# telescopicrobot.net
KiCad netlist of a schematic drawn in EAGLE
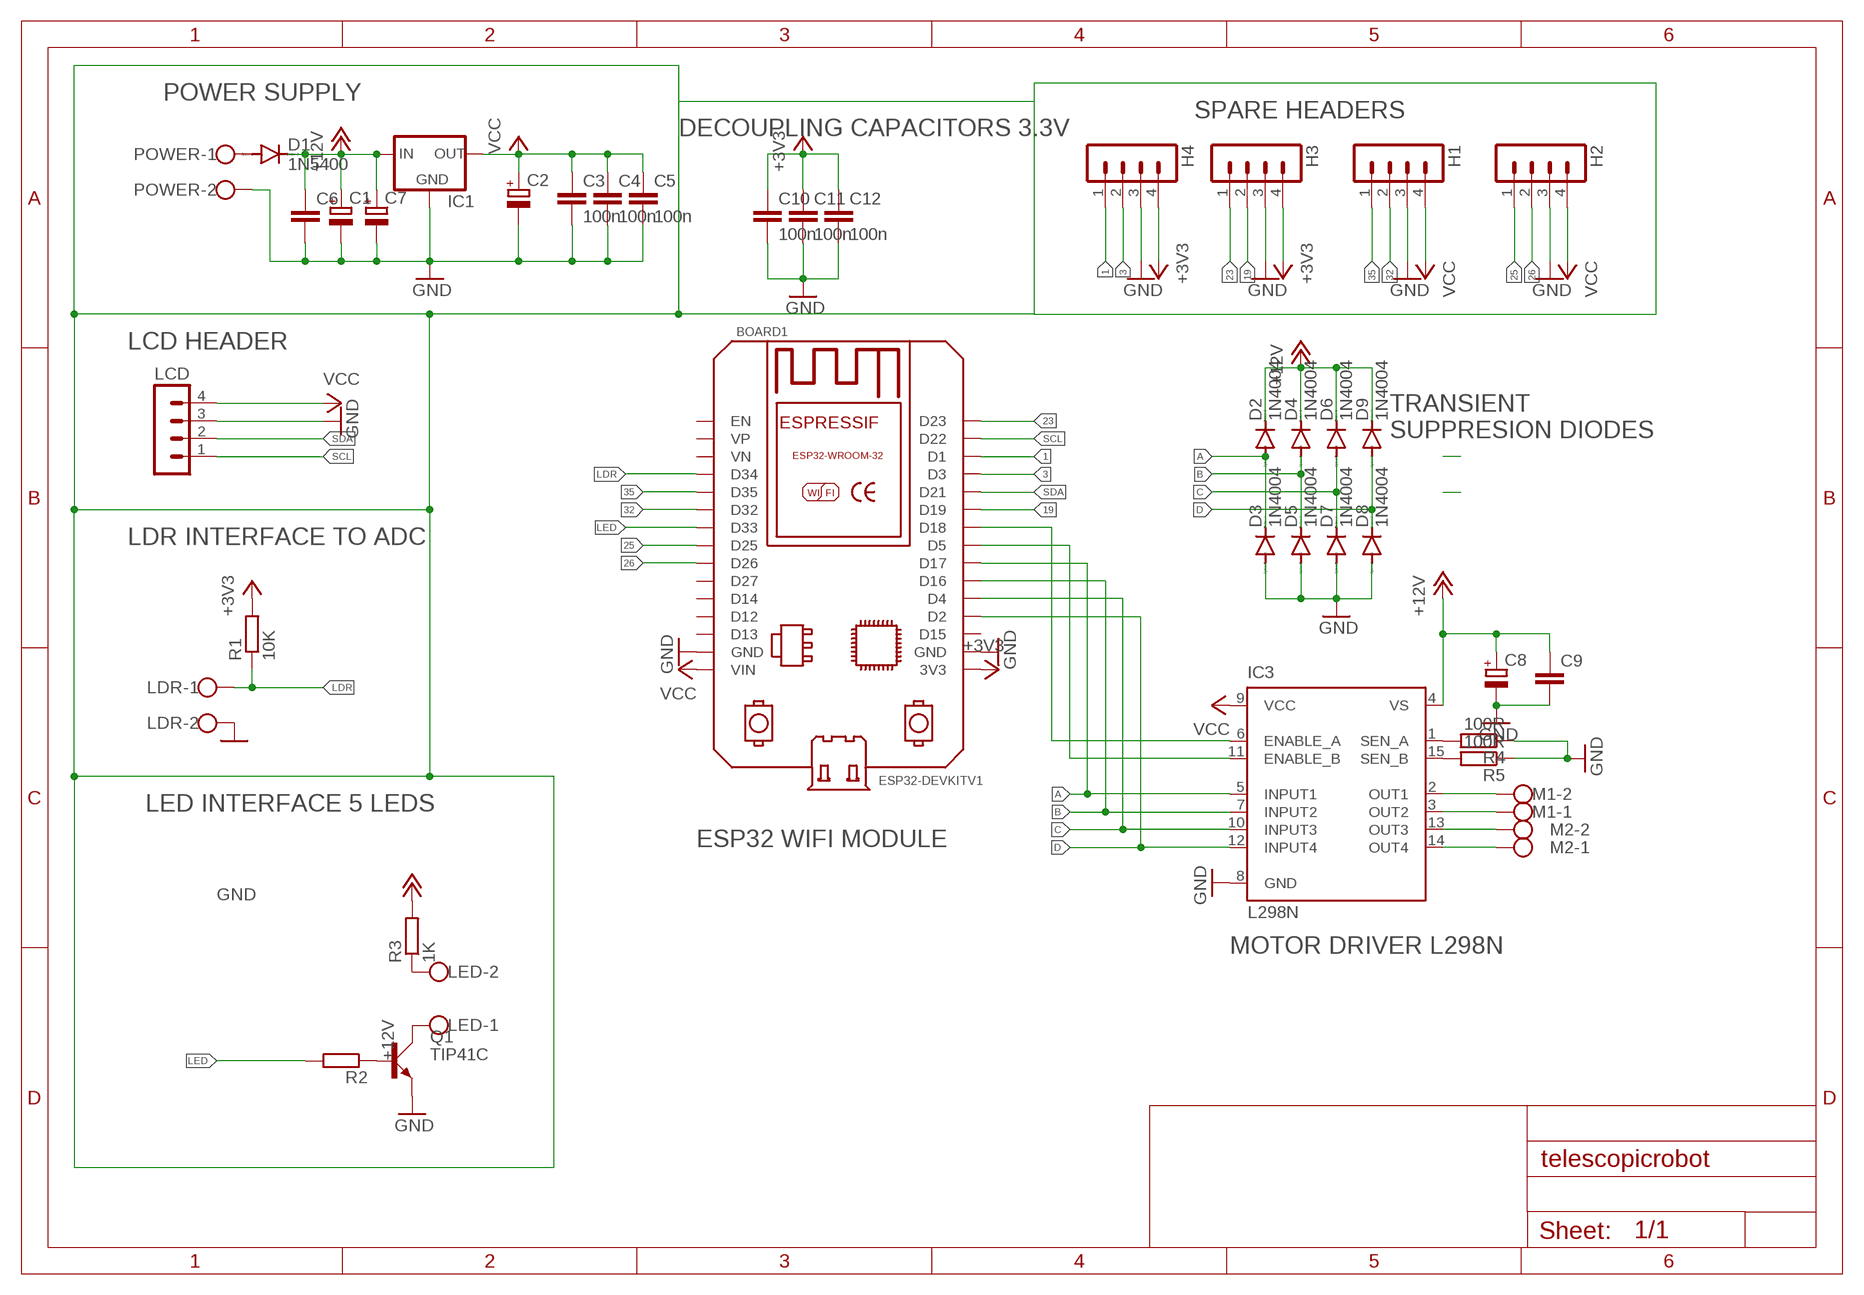
[diagram p0: schematic, sheet 1]

(export (version "E")
  (design (tool "Eeschema 10.0.6"))
  (components
    (comp (ref "BOARD1")
      (value "ESP32DEVKITV1")
      (footprint "eagle-import:ESP32-DEVKITV1")
      (libsource (lib "eagle-import") (part "ESP32DEVKITV1"))
    )
    (comp (ref "C1")
      (value "CPOL-EUE5-10.5")
      (footprint "eagle-import:E5-10,5")
      (libsource (lib "eagle-import") (part "CPOL-EUE5-10.5"))
    )
    (comp (ref "C2")
      (value "CPOL-EUE2.5-5")
      (footprint "eagle-import:E2,5-5")
      (libsource (lib "eagle-import") (part "CPOL-EUE2.5-5"))
    )
    (comp (ref "C3")
      (value "100n")
      (footprint "eagle-import:C2.5-3")
      (libsource (lib "eagle-import") (part "C2,5-3"))
    )
    (comp (ref "C4")
      (value "100n")
      (footprint "eagle-import:C2.5-3")
      (libsource (lib "eagle-import") (part "C2,5-3"))
    )
    (comp (ref "C5")
      (value "100n")
      (footprint "eagle-import:C2.5-3")
      (libsource (lib "eagle-import") (part "C2,5-3"))
    )
    (comp (ref "C6")
      (value "C2,5-3")
      (footprint "eagle-import:C2.5-3")
      (libsource (lib "eagle-import") (part "C2,5-3"))
    )
    (comp (ref "C7")
      (value "CPOL-EUE5-10.5")
      (footprint "eagle-import:E5-10,5")
      (libsource (lib "eagle-import") (part "CPOL-EUE5-10.5"))
    )
    (comp (ref "C8")
      (value "CPOL-EUE5-10.5")
      (footprint "eagle-import:E5-10,5")
      (libsource (lib "eagle-import") (part "CPOL-EUE5-10.5"))
    )
    (comp (ref "C9")
      (value "C2,5-3")
      (footprint "eagle-import:C2.5-3")
      (libsource (lib "eagle-import") (part "C2,5-3"))
    )
    (comp (ref "C10")
      (value "100n")
      (footprint "eagle-import:C2.5-3")
      (libsource (lib "eagle-import") (part "C2,5-3"))
    )
    (comp (ref "C11")
      (value "100n")
      (footprint "eagle-import:C2.5-3")
      (libsource (lib "eagle-import") (part "C2,5-3"))
    )
    (comp (ref "C12")
      (value "100n")
      (footprint "eagle-import:C2.5-3")
      (libsource (lib "eagle-import") (part "C2,5-3"))
    )
    (comp (ref "D1")
      (value "1N5400")
      (footprint "eagle-import:DO201-15")
      (libsource (lib "eagle-import") (part "1N5400"))
    )
    (comp (ref "D2")
      (value "1N4004")
      (footprint "eagle-import:DO41-10")
      (libsource (lib "eagle-import") (part "1N4004"))
    )
    (comp (ref "D3")
      (value "1N4004")
      (footprint "eagle-import:DO41-10")
      (libsource (lib "eagle-import") (part "1N4004"))
    )
    (comp (ref "D4")
      (value "1N4004")
      (footprint "eagle-import:DO41-10")
      (libsource (lib "eagle-import") (part "1N4004"))
    )
    (comp (ref "D5")
      (value "1N4004")
      (footprint "eagle-import:DO41-10")
      (libsource (lib "eagle-import") (part "1N4004"))
    )
    (comp (ref "D6")
      (value "1N4004")
      (footprint "eagle-import:DO41-10")
      (libsource (lib "eagle-import") (part "1N4004"))
    )
    (comp (ref "D7")
      (value "1N4004")
      (footprint "eagle-import:DO41-10")
      (libsource (lib "eagle-import") (part "1N4004"))
    )
    (comp (ref "D8")
      (value "1N4004")
      (footprint "eagle-import:DO41-10")
      (libsource (lib "eagle-import") (part "1N4004"))
    )
    (comp (ref "D9")
      (value "1N4004")
      (footprint "eagle-import:DO41-10")
      (libsource (lib "eagle-import") (part "1N4004"))
    )
    (comp (ref "H1")
      (value "MA04-1")
      (footprint "eagle-import:MA04-1")
      (libsource (lib "eagle-import") (part "MA04-1"))
    )
    (comp (ref "H2")
      (value "MA04-1")
      (footprint "eagle-import:MA04-1")
      (libsource (lib "eagle-import") (part "MA04-1"))
    )
    (comp (ref "H3")
      (value "MA04-1")
      (footprint "eagle-import:MA04-1")
      (libsource (lib "eagle-import") (part "MA04-1"))
    )
    (comp (ref "H4")
      (value "MA04-1")
      (footprint "eagle-import:MA04-1")
      (libsource (lib "eagle-import") (part "MA04-1"))
    )
    (comp (ref "IC1")
      (value "78XXS")
      (footprint "eagle-import:78XXS")
      (libsource (lib "eagle-import") (part "78XXS"))
    )
    (comp (ref "IC3")
      (value "L298N")
      (footprint "eagle-import:MULTIWATT-15")
      (libsource (lib "eagle-import") (part "L298N"))
    )
    (comp (ref "LCD")
      (value "MA04-1")
      (footprint "eagle-import:MA04-1")
      (libsource (lib "eagle-import") (part "MA04-1"))
    )
    (comp (ref "LDR")
      (value "W237-102")
      (footprint "eagle-import:W237-102")
      (fields (field (name "MPN") "237-102"))
      (libsource (lib "eagle-import") (part "W237-102"))
    )
    (comp (ref "LED")
      (value "W237-102")
      (footprint "eagle-import:W237-102")
      (fields (field (name "MPN") "237-102"))
      (libsource (lib "eagle-import") (part "W237-102"))
    )
    (comp (ref "M1")
      (value "W237-102")
      (footprint "eagle-import:W237-102")
      (fields (field (name "MPN") "237-102"))
      (libsource (lib "eagle-import") (part "W237-102"))
    )
    (comp (ref "M2")
      (value "W237-102")
      (footprint "eagle-import:W237-102")
      (fields (field (name "MPN") "237-102"))
      (libsource (lib "eagle-import") (part "W237-102"))
    )
    (comp (ref "POWER")
      (value "W237-102")
      (footprint "eagle-import:W237-102")
      (fields (field (name "MPN") "237-102"))
      (libsource (lib "eagle-import") (part "W237-102"))
    )
    (comp (ref "Q1")
      (value "TIP41C")
      (footprint "eagle-import:TO220AV")
      (libsource (lib "eagle-import") (part "TIP41C"))
    )
    (comp (ref "R1")
      (value "10K")
      (footprint "eagle-import:0207_12")
      (libsource (lib "eagle-import") (part "R-EU_0207/12"))
    )
    (comp (ref "R2")
      (value "R-EU_0207/12")
      (footprint "eagle-import:0207_12")
      (libsource (lib "eagle-import") (part "R-EU_0207/12"))
    )
    (comp (ref "R3")
      (value "1K")
      (footprint "eagle-import:0207_12")
      (libsource (lib "eagle-import") (part "resistor_348_R-EU_0207/12"))
    )
    (comp (ref "R4")
      (value "100R")
      (footprint "eagle-import:0207_12")
      (libsource (lib "eagle-import") (part "resistor_348_R-EU_0207/12"))
    )
    (comp (ref "R5")
      (value "100R")
      (footprint "eagle-import:0207_12")
      (libsource (lib "eagle-import") (part "resistor_348_R-EU_0207/12"))
    )
  )
  (nets
    (net (code "1") (name "+3V3") (class "Default")
      (node (ref "BOARD1") (pin "3V3") (pinfunction "3V3_3V3") (pintype "bidirectional"))
      (node (ref "C10") (pin "1") (pinfunction "1_1") (pintype "passive"))
      (node (ref "C11") (pin "1") (pinfunction "1_1") (pintype "passive"))
      (node (ref "C12") (pin "1") (pinfunction "1_1") (pintype "passive"))
      (node (ref "H3") (pin "4") (pinfunction "4_4") (pintype "passive"))
      (node (ref "H4") (pin "4") (pinfunction "4_4") (pintype "passive"))
      (node (ref "R1") (pin "2") (pinfunction "2_2") (pintype "passive"))
    )
    (net (code "2") (name "+12V") (class "Default")
      (node (ref "C1") (pin "+") (pinfunction "+_+") (pintype "passive"))
      (node (ref "C6") (pin "1") (pinfunction "1_1") (pintype "passive"))
      (node (ref "C7") (pin "+") (pinfunction "+_+") (pintype "passive"))
      (node (ref "C8") (pin "+") (pinfunction "+_+") (pintype "passive"))
      (node (ref "C9") (pin "1") (pinfunction "1_1") (pintype "passive"))
      (node (ref "D1") (pin "C") (pinfunction "C_C") (pintype "passive"))
      (node (ref "D2") (pin "C") (pinfunction "C_C") (pintype "passive"))
      (node (ref "D4") (pin "C") (pinfunction "C_C") (pintype "passive"))
      (node (ref "D6") (pin "C") (pinfunction "C_C") (pintype "passive"))
      (node (ref "D9") (pin "C") (pinfunction "C_C") (pintype "passive"))
      (node (ref "IC1") (pin "IN") (pinfunction "IN_IN") (pintype "input"))
      (node (ref "IC3") (pin "4") (pinfunction "VS_4") (pintype "power_in"))
      (node (ref "R3") (pin "2") (pinfunction "2_2") (pintype "passive"))
    )
    (net (code "3") (name "1") (class "Default")
      (node (ref "BOARD1") (pin "D1") (pinfunction "D1_D1") (pintype "bidirectional"))
      (node (ref "H4") (pin "1") (pinfunction "1_1") (pintype "passive"))
    )
    (net (code "4") (name "3") (class "Default")
      (node (ref "BOARD1") (pin "D3") (pinfunction "D3_D3") (pintype "bidirectional"))
      (node (ref "H4") (pin "2") (pinfunction "2_2") (pintype "passive"))
    )
    (net (code "5") (name "19") (class "Default")
      (node (ref "BOARD1") (pin "D19") (pinfunction "D19_D19") (pintype "bidirectional"))
      (node (ref "H3") (pin "2") (pinfunction "2_2") (pintype "passive"))
    )
    (net (code "6") (name "23") (class "Default")
      (node (ref "BOARD1") (pin "D23") (pinfunction "D23_D23") (pintype "bidirectional"))
      (node (ref "H3") (pin "1") (pinfunction "1_1") (pintype "passive"))
    )
    (net (code "7") (name "25") (class "Default")
      (node (ref "BOARD1") (pin "D25") (pinfunction "D25_D25") (pintype "bidirectional"))
      (node (ref "H2") (pin "1") (pinfunction "1_1") (pintype "passive"))
    )
    (net (code "8") (name "26") (class "Default")
      (node (ref "BOARD1") (pin "D26") (pinfunction "D26_D26") (pintype "bidirectional"))
      (node (ref "H2") (pin "2") (pinfunction "2_2") (pintype "passive"))
    )
    (net (code "9") (name "32") (class "Default")
      (node (ref "BOARD1") (pin "D32") (pinfunction "D32_D32") (pintype "bidirectional"))
      (node (ref "H1") (pin "2") (pinfunction "2_2") (pintype "passive"))
    )
    (net (code "10") (name "35") (class "Default")
      (node (ref "BOARD1") (pin "D35") (pinfunction "D35_D35") (pintype "bidirectional"))
      (node (ref "H1") (pin "1") (pinfunction "1_1") (pintype "passive"))
    )
    (net (code "11") (name "A") (class "Default")
      (node (ref "BOARD1") (pin "D17") (pinfunction "D17_D17") (pintype "bidirectional"))
      (node (ref "D2") (pin "A") (pinfunction "A_A") (pintype "passive"))
      (node (ref "D3") (pin "C") (pinfunction "C_C") (pintype "passive"))
      (node (ref "IC3") (pin "5") (pinfunction "INPUT1_5") (pintype "input"))
    )
    (net (code "12") (name "B") (class "Default")
      (node (ref "BOARD1") (pin "D16") (pinfunction "D16_D16") (pintype "bidirectional"))
      (node (ref "D4") (pin "A") (pinfunction "A_A") (pintype "passive"))
      (node (ref "D5") (pin "C") (pinfunction "C_C") (pintype "passive"))
      (node (ref "IC3") (pin "7") (pinfunction "INPUT2_7") (pintype "input"))
    )
    (net (code "13") (name "C") (class "Default")
      (node (ref "BOARD1") (pin "D4") (pinfunction "D4_D4") (pintype "bidirectional"))
      (node (ref "D6") (pin "A") (pinfunction "A_A") (pintype "passive"))
      (node (ref "D7") (pin "C") (pinfunction "C_C") (pintype "passive"))
      (node (ref "IC3") (pin "10") (pinfunction "INPUT3_10") (pintype "input"))
    )
    (net (code "14") (name "D") (class "Default")
      (node (ref "BOARD1") (pin "D2") (pinfunction "D2_D2") (pintype "bidirectional"))
      (node (ref "D8") (pin "C") (pinfunction "C_C") (pintype "passive"))
      (node (ref "D9") (pin "A") (pinfunction "A_A") (pintype "passive"))
      (node (ref "IC3") (pin "12") (pinfunction "INPUT4_12") (pintype "input"))
    )
    (net (code "15") (name "GND") (class "Default")
      (node (ref "BOARD1") (pin "GND") (pinfunction "GND_GND") (pintype "bidirectional"))
      (node (ref "BOARD1") (pin "GND@1") (pinfunction "GND_GND@1") (pintype "bidirectional"))
      (node (ref "C1") (pin "-") (pinfunction "-_-") (pintype "passive"))
      (node (ref "C10") (pin "2") (pinfunction "2_2") (pintype "passive"))
      (node (ref "C11") (pin "2") (pinfunction "2_2") (pintype "passive"))
      (node (ref "C12") (pin "2") (pinfunction "2_2") (pintype "passive"))
      (node (ref "C2") (pin "-") (pinfunction "-_-") (pintype "passive"))
      (node (ref "C3") (pin "2") (pinfunction "2_2") (pintype "passive"))
      (node (ref "C4") (pin "2") (pinfunction "2_2") (pintype "passive"))
      (node (ref "C5") (pin "2") (pinfunction "2_2") (pintype "passive"))
      (node (ref "C6") (pin "2") (pinfunction "2_2") (pintype "passive"))
      (node (ref "C7") (pin "-") (pinfunction "-_-") (pintype "passive"))
      (node (ref "C8") (pin "-") (pinfunction "-_-") (pintype "passive"))
      (node (ref "C9") (pin "2") (pinfunction "2_2") (pintype "passive"))
      (node (ref "D3") (pin "A") (pinfunction "A_A") (pintype "passive"))
      (node (ref "D5") (pin "A") (pinfunction "A_A") (pintype "passive"))
      (node (ref "D7") (pin "A") (pinfunction "A_A") (pintype "passive"))
      (node (ref "D8") (pin "A") (pinfunction "A_A") (pintype "passive"))
      (node (ref "H1") (pin "3") (pinfunction "3_3") (pintype "passive"))
      (node (ref "H2") (pin "3") (pinfunction "3_3") (pintype "passive"))
      (node (ref "H3") (pin "3") (pinfunction "3_3") (pintype "passive"))
      (node (ref "H4") (pin "3") (pinfunction "3_3") (pintype "passive"))
      (node (ref "IC1") (pin "GND") (pinfunction "GND_GND") (pintype "input"))
      (node (ref "IC3") (pin "8") (pinfunction "GND_8") (pintype "power_in"))
      (node (ref "LCD") (pin "3") (pinfunction "3_3") (pintype "passive"))
      (node (ref "LDR") (pin "2") (pinfunction "KL_2") (pintype "passive"))
      (node (ref "POWER") (pin "2") (pinfunction "KL_2") (pintype "passive"))
      (node (ref "Q1") (pin "E") (pinfunction "E_E") (pintype "passive"))
      (node (ref "R4") (pin "1") (pinfunction "1_1") (pintype "passive"))
      (node (ref "R5") (pin "1") (pinfunction "1_1") (pintype "passive"))
    )
    (net (code "16") (name "LDR") (class "Default")
      (node (ref "BOARD1") (pin "D34") (pinfunction "D34_D34") (pintype "bidirectional"))
      (node (ref "LDR") (pin "1") (pinfunction "KL_1") (pintype "passive"))
      (node (ref "R1") (pin "1") (pinfunction "1_1") (pintype "passive"))
    )
    (net (code "17") (name "LED") (class "Default")
      (node (ref "BOARD1") (pin "D33") (pinfunction "D33_D33") (pintype "bidirectional"))
      (node (ref "R2") (pin "2") (pinfunction "2_2") (pintype "passive"))
    )
    (net (code "18") (name "Net-(IC3-ENABLE_A)") (class "Default")
      (node (ref "BOARD1") (pin "D18") (pinfunction "D18_D18") (pintype "bidirectional"))
      (node (ref "IC3") (pin "6") (pinfunction "ENABLE_A_6") (pintype "input"))
    )
    (net (code "19") (name "Net-(IC3-ENABLE_B)") (class "Default")
      (node (ref "BOARD1") (pin "D5") (pinfunction "D5_D5") (pintype "bidirectional"))
      (node (ref "IC3") (pin "11") (pinfunction "ENABLE_B_11") (pintype "input"))
    )
    (net (code "20") (name "Net-(IC3-OUT1)") (class "Default")
      (node (ref "IC3") (pin "2") (pinfunction "OUT1_2") (pintype "output"))
      (node (ref "M1") (pin "2") (pinfunction "KL_2") (pintype "passive"))
    )
    (net (code "21") (name "Net-(IC3-OUT2)") (class "Default")
      (node (ref "IC3") (pin "3") (pinfunction "OUT2_3") (pintype "output"))
      (node (ref "M1") (pin "1") (pinfunction "KL_1") (pintype "passive"))
    )
    (net (code "22") (name "Net-(IC3-OUT3)") (class "Default")
      (node (ref "IC3") (pin "13") (pinfunction "OUT3_13") (pintype "output"))
      (node (ref "M2") (pin "2") (pinfunction "KL_2") (pintype "passive"))
    )
    (net (code "23") (name "Net-(IC3-OUT4)") (class "Default")
      (node (ref "IC3") (pin "14") (pinfunction "OUT4_14") (pintype "output"))
      (node (ref "M2") (pin "1") (pinfunction "KL_1") (pintype "passive"))
    )
    (net (code "24") (name "Net-(IC3-SEN_A)") (class "Default")
      (node (ref "IC3") (pin "1") (pinfunction "SEN_A_1") (pintype "input"))
      (node (ref "R4") (pin "2") (pinfunction "2_2") (pintype "passive"))
    )
    (net (code "25") (name "Net-(IC3-SEN_B)") (class "Default")
      (node (ref "IC3") (pin "15") (pinfunction "SEN_B_15") (pintype "input"))
      (node (ref "R5") (pin "2") (pinfunction "2_2") (pintype "passive"))
    )
    (net (code "26") (name "Net-(LEDA-KL)") (class "Default")
      (node (ref "LED") (pin "1") (pinfunction "KL_1") (pintype "passive"))
      (node (ref "Q1") (pin "C") (pinfunction "C_C") (pintype "passive"))
    )
    (net (code "27") (name "Net-(LEDB-KL)") (class "Default")
      (node (ref "LED") (pin "2") (pinfunction "KL_2") (pintype "passive"))
      (node (ref "R3") (pin "1") (pinfunction "1_1") (pintype "passive"))
    )
    (net (code "28") (name "Net-(POWERA-KL)") (class "Default")
      (node (ref "D1") (pin "A") (pinfunction "A_A") (pintype "passive"))
      (node (ref "POWER") (pin "1") (pinfunction "KL_1") (pintype "passive"))
    )
    (net (code "29") (name "Net-(Q1-PadB)") (class "Default")
      (node (ref "Q1") (pin "B") (pinfunction "B_B") (pintype "passive"))
      (node (ref "R2") (pin "1") (pinfunction "1_1") (pintype "passive"))
    )
    (net (code "30") (name "SCL") (class "Default")
      (node (ref "BOARD1") (pin "D22") (pinfunction "D22_D22") (pintype "bidirectional"))
      (node (ref "LCD") (pin "1") (pinfunction "1_1") (pintype "passive"))
    )
    (net (code "31") (name "SDA") (class "Default")
      (node (ref "BOARD1") (pin "D21") (pinfunction "D21_D21") (pintype "bidirectional"))
      (node (ref "LCD") (pin "2") (pinfunction "2_2") (pintype "passive"))
    )
    (net (code "32") (name "VCC") (class "Default")
      (node (ref "BOARD1") (pin "VIN") (pinfunction "VIN_VIN") (pintype "bidirectional"))
      (node (ref "C2") (pin "+") (pinfunction "+_+") (pintype "passive"))
      (node (ref "C3") (pin "1") (pinfunction "1_1") (pintype "passive"))
      (node (ref "C4") (pin "1") (pinfunction "1_1") (pintype "passive"))
      (node (ref "C5") (pin "1") (pinfunction "1_1") (pintype "passive"))
      (node (ref "H1") (pin "4") (pinfunction "4_4") (pintype "passive"))
      (node (ref "H2") (pin "4") (pinfunction "4_4") (pintype "passive"))
      (node (ref "IC1") (pin "OUT") (pinfunction "OUT_OUT") (pintype "passive"))
      (node (ref "IC3") (pin "9") (pinfunction "VCC_9") (pintype "power_in"))
      (node (ref "LCD") (pin "4") (pinfunction "4_4") (pintype "passive"))
    )
    (net (code "33") (name "unconnected-(BOARD1-PadD12)") (class "Default")
      (node (ref "BOARD1") (pin "D12") (pinfunction "D12_D12") (pintype "bidirectional"))
    )
    (net (code "34") (name "unconnected-(BOARD1-PadD13)") (class "Default")
      (node (ref "BOARD1") (pin "D13") (pinfunction "D13_D13") (pintype "bidirectional"))
    )
    (net (code "35") (name "unconnected-(BOARD1-PadD14)") (class "Default")
      (node (ref "BOARD1") (pin "D14") (pinfunction "D14_D14") (pintype "bidirectional"))
    )
    (net (code "36") (name "unconnected-(BOARD1-PadD15)") (class "Default")
      (node (ref "BOARD1") (pin "D15") (pinfunction "D15_D15") (pintype "bidirectional"))
    )
    (net (code "37") (name "unconnected-(BOARD1-PadD27)") (class "Default")
      (node (ref "BOARD1") (pin "D27") (pinfunction "D27_D27") (pintype "bidirectional"))
    )
    (net (code "38") (name "unconnected-(BOARD1-PadEN)") (class "Default")
      (node (ref "BOARD1") (pin "EN") (pinfunction "EN_EN") (pintype "bidirectional"))
    )
    (net (code "39") (name "unconnected-(BOARD1-PadVN)") (class "Default")
      (node (ref "BOARD1") (pin "VN") (pinfunction "VN_VN") (pintype "bidirectional"))
    )
    (net (code "40") (name "unconnected-(BOARD1-PadVP)") (class "Default")
      (node (ref "BOARD1") (pin "VP") (pinfunction "VP_VP") (pintype "bidirectional"))
    )
  )
)
